# Estl-Board.net
KiCad netlist of a schematic drawn in EAGLE
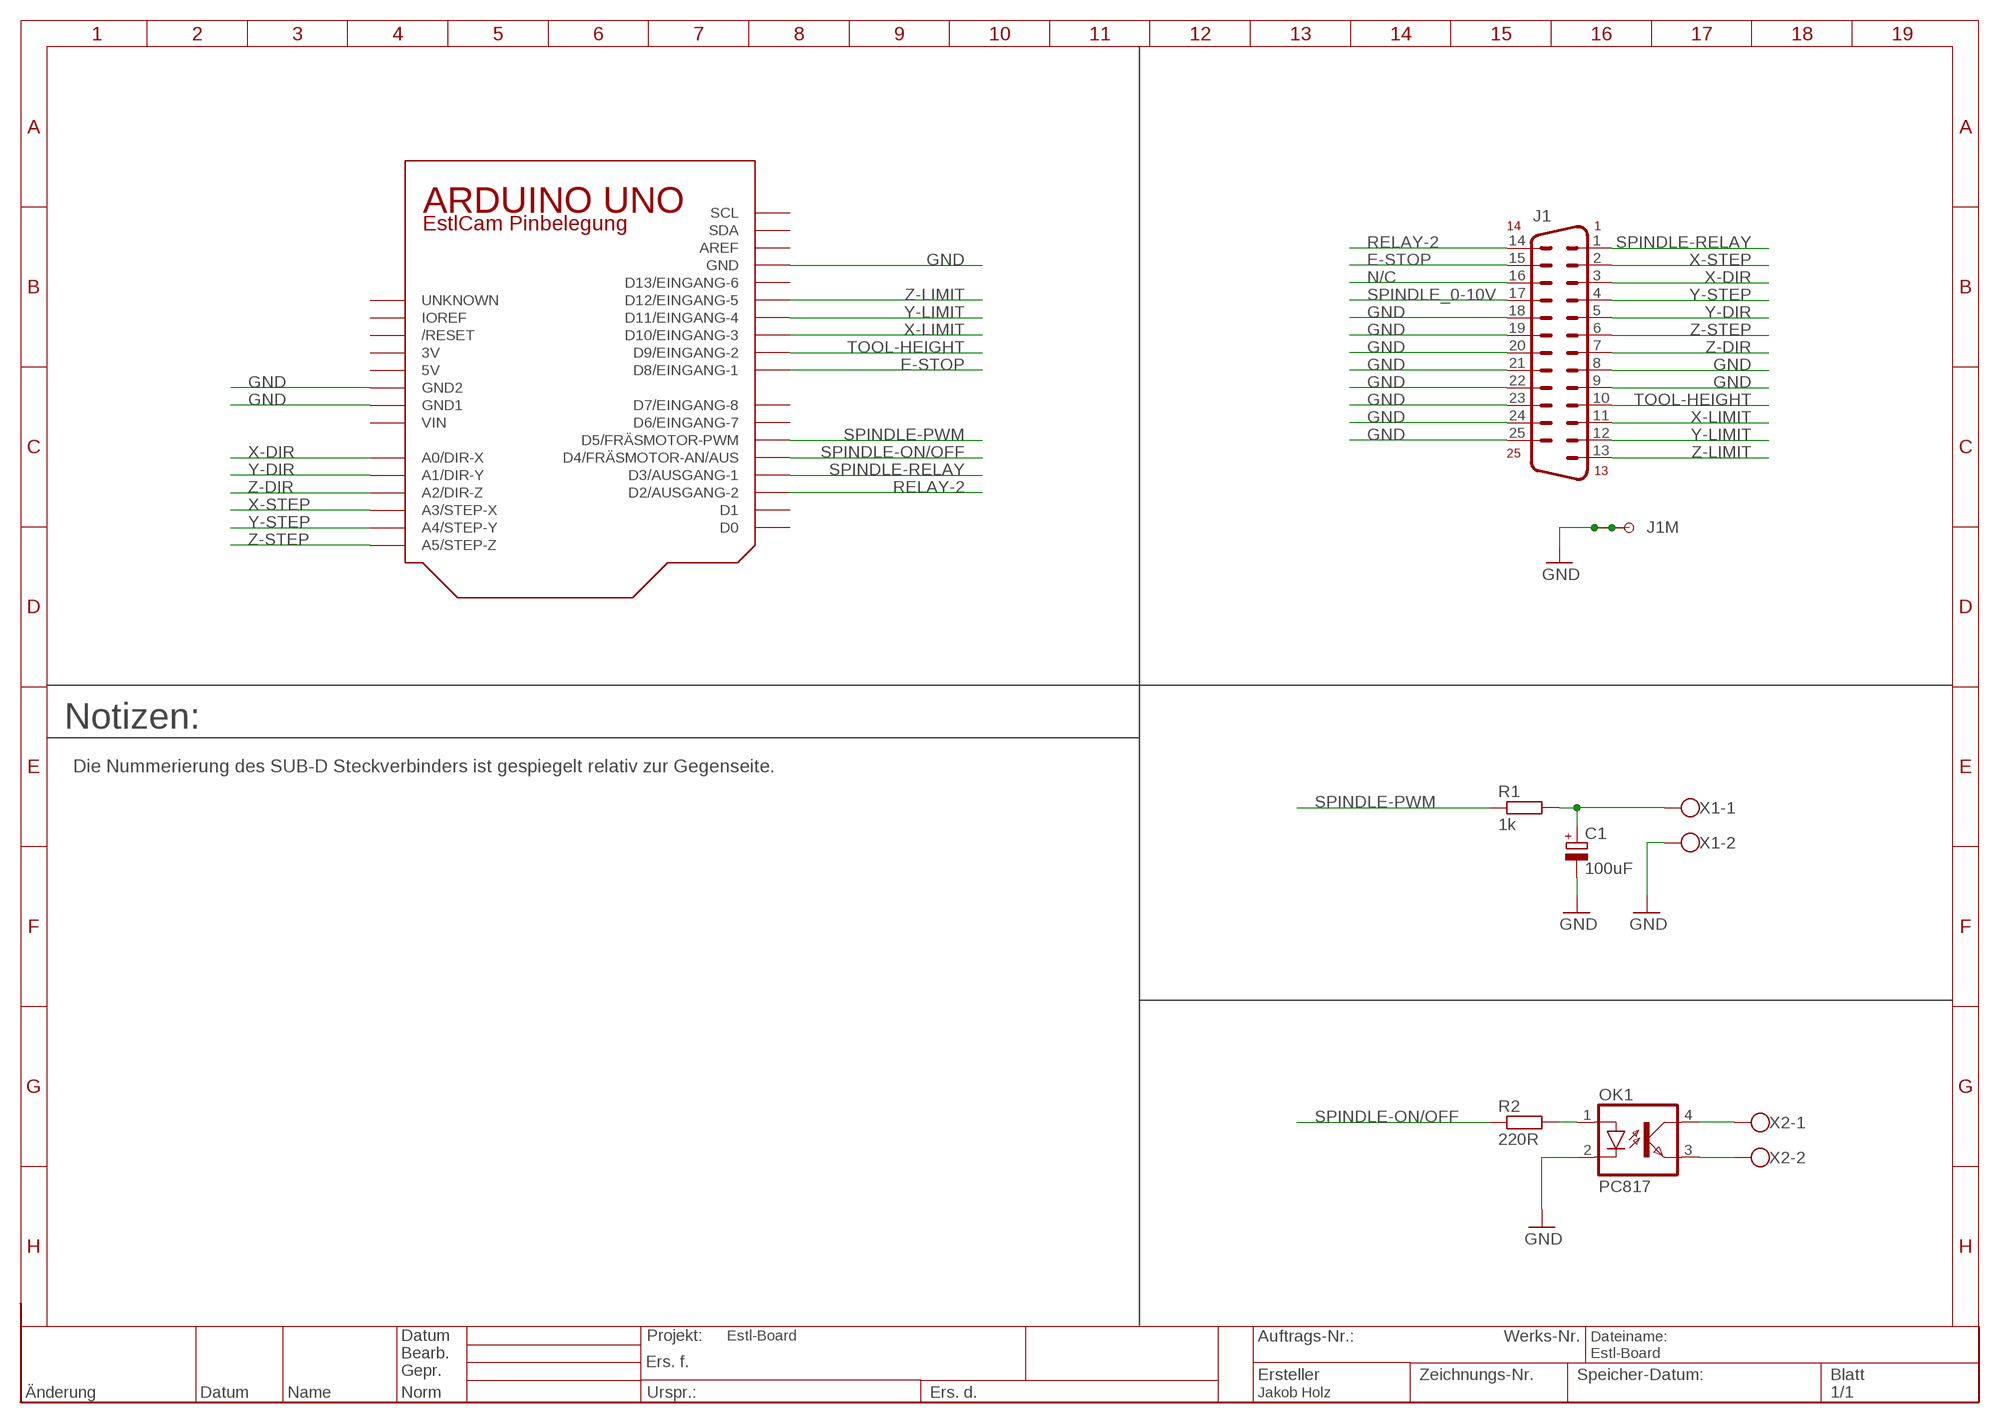
[diagram p0: schematic, sheet 1]

(export (version "E")
  (design (tool "Eeschema 10.0.6"))
  (components
    (comp (ref "C1")
      (value "100uF")
      (footprint "eagle-import:E2-5-CAM")
      (libsource (lib "eagle-import") (part "CPOL-EU-CAM"))
    )
    (comp (ref "IC1")
      (value "ARDUINO")
      (footprint "eagle-import:ARDUINO_NOHOLES")
      (libsource (lib "eagle-import") (part "ARDUINO"))
    )
    (comp (ref "J1")
      (value "JP-316B")
      (footprint "eagle-import:M25HP")
      (libsource (lib "eagle-import") (part "JP-316B"))
    )
    (comp (ref "OK1")
      (value "PC817")
      (footprint "eagle-import:DIP4")
      (libsource (lib "eagle-import") (part "PC817"))
    )
    (comp (ref "R1")
      (value "1k")
      (footprint "eagle-import:207_10+")
      (libsource (lib "eagle-import") (part "R-EU-CAM"))
    )
    (comp (ref "R2")
      (value "220R")
      (footprint "eagle-import:207_10+")
      (libsource (lib "eagle-import") (part "R-EU-CAM"))
    )
    (comp (ref "X1")
      (value "W237-102")
      (footprint "eagle-import:W237-102")
      (fields (field (name "MPN") "237-102"))
      (libsource (lib "eagle-import") (part "W237-102"))
    )
    (comp (ref "X2")
      (value "W237-102")
      (footprint "eagle-import:W237-102")
      (fields (field (name "MPN") "237-102"))
      (libsource (lib "eagle-import") (part "W237-102"))
    )
  )
  (nets
    (net (code "1") (name "/3V") (class "Default")
      (node (ref "IC1") (pin "3V") (pinfunction "3V_3V") (pintype "power_in"))
    )
    (net (code "2") (name "/5V") (class "Default")
      (node (ref "IC1") (pin "5V") (pinfunction "5V_5V") (pintype "power_in"))
    )
    (net (code "3") (name "/E-STOP") (class "Default")
      (node (ref "IC1") (pin "D8") (pinfunction "D8/EINGANG-1_D8") (pintype "bidirectional"))
      (node (ref "J1") (pin "15") (pinfunction "E-STOP_15") (pintype "passive"))
    )
    (net (code "4") (name "/N{slash}C") (class "Default")
      (node (ref "J1") (pin "16") (pinfunction "N/C_16") (pintype "passive"))
    )
    (net (code "5") (name "/RELAY-2") (class "Default")
      (node (ref "IC1") (pin "D2") (pinfunction "D2/AUSGANG-2_D2") (pintype "bidirectional"))
      (node (ref "J1") (pin "14") (pinfunction "RELAY-2_14") (pintype "passive"))
    )
    (net (code "6") (name "/SPINDLE-ON{slash}OFF") (class "Default")
      (node (ref "IC1") (pin "D4") (pinfunction "D4/FRÄSMOTOR-AN/AUS_D4") (pintype "bidirectional"))
      (node (ref "R2") (pin "1") (pinfunction "1_1") (pintype "passive"))
    )
    (net (code "7") (name "/SPINDLE-PWM") (class "Default")
      (node (ref "IC1") (pin "D5") (pinfunction "D5/FRÄSMOTOR-PWM_D5") (pintype "bidirectional"))
      (node (ref "R1") (pin "1") (pinfunction "1_1") (pintype "passive"))
    )
    (net (code "8") (name "/SPINDLE-RELAY") (class "Default")
      (node (ref "IC1") (pin "D3") (pinfunction "D3/AUSGANG-1_D3") (pintype "bidirectional"))
      (node (ref "J1") (pin "1") (pinfunction "SPINDLE-RELAY_1") (pintype "passive"))
    )
    (net (code "9") (name "/SPINDLE_0-10V") (class "Default")
      (node (ref "J1") (pin "17") (pinfunction "SPINDLE_0-10V_17") (pintype "passive"))
    )
    (net (code "10") (name "/TOOL-HEIGHT") (class "Default")
      (node (ref "IC1") (pin "D9") (pinfunction "D9/EINGANG-2_D9") (pintype "bidirectional"))
      (node (ref "J1") (pin "10") (pinfunction "TOOL-HEIGHT_10") (pintype "passive"))
    )
    (net (code "11") (name "/VIN") (class "Default")
      (node (ref "IC1") (pin "VIN") (pinfunction "VIN_VIN") (pintype "power_in"))
    )
    (net (code "12") (name "/X-DIR") (class "Default")
      (node (ref "IC1") (pin "A0") (pinfunction "A0/DIR-X_A0") (pintype "bidirectional"))
      (node (ref "J1") (pin "3") (pinfunction "X-DIR_3") (pintype "passive"))
    )
    (net (code "13") (name "/X-LIMIT") (class "Default")
      (node (ref "IC1") (pin "D10") (pinfunction "D10/EINGANG-3_D10") (pintype "bidirectional"))
      (node (ref "J1") (pin "11") (pinfunction "X-LIMIT_11") (pintype "passive"))
    )
    (net (code "14") (name "/X-STEP") (class "Default")
      (node (ref "IC1") (pin "A3") (pinfunction "A3/STEP-X_A3") (pintype "bidirectional"))
      (node (ref "J1") (pin "2") (pinfunction "X-STEP_2") (pintype "passive"))
    )
    (net (code "15") (name "/Y-DIR") (class "Default")
      (node (ref "IC1") (pin "A1") (pinfunction "A1/DIR-Y_A1") (pintype "bidirectional"))
      (node (ref "J1") (pin "5") (pinfunction "Y-DIR_5") (pintype "passive"))
    )
    (net (code "16") (name "/Y-LIMIT") (class "Default")
      (node (ref "IC1") (pin "D11") (pinfunction "D11/EINGANG-4_D11") (pintype "bidirectional"))
      (node (ref "J1") (pin "12") (pinfunction "Y-LIMIT_12") (pintype "passive"))
    )
    (net (code "17") (name "/Y-STEP") (class "Default")
      (node (ref "IC1") (pin "A4") (pinfunction "A4/STEP-Y_A4") (pintype "bidirectional"))
      (node (ref "J1") (pin "4") (pinfunction "Y-STEP_4") (pintype "passive"))
    )
    (net (code "18") (name "/Z-DIR") (class "Default")
      (node (ref "IC1") (pin "A2") (pinfunction "A2/DIR-Z_A2") (pintype "bidirectional"))
      (node (ref "J1") (pin "7") (pinfunction "Z-DIR_7") (pintype "passive"))
    )
    (net (code "19") (name "/Z-LIMIT") (class "Default")
      (node (ref "IC1") (pin "D12") (pinfunction "D12/EINGANG-5_D12") (pintype "bidirectional"))
      (node (ref "J1") (pin "13") (pinfunction "Z-LIMIT_13") (pintype "passive"))
    )
    (net (code "20") (name "/Z-STEP") (class "Default")
      (node (ref "IC1") (pin "A5") (pinfunction "A5/STEP-Z_A5") (pintype "bidirectional"))
      (node (ref "J1") (pin "6") (pinfunction "Z-STEP_6") (pintype "passive"))
    )
    (net (code "21") (name "GND") (class "Default")
      (node (ref "C1") (pin "-") (pinfunction "-_-") (pintype "passive"))
      (node (ref "IC1") (pin "GND") (pinfunction "GND_GND") (pintype "power_in"))
      (node (ref "IC1") (pin "GND1") (pinfunction "GND1_GND1") (pintype "power_in"))
      (node (ref "IC1") (pin "GND2") (pinfunction "GND2_GND2") (pintype "power_in"))
      (node (ref "J1") (pin "18") (pinfunction "GND0_18") (pintype "passive"))
      (node (ref "J1") (pin "19") (pinfunction "GND1_19") (pintype "passive"))
      (node (ref "J1") (pin "20") (pinfunction "GND2_20") (pintype "passive"))
      (node (ref "J1") (pin "21") (pinfunction "GND3_21") (pintype "passive"))
      (node (ref "J1") (pin "22") (pinfunction "GND4_22") (pintype "passive"))
      (node (ref "J1") (pin "23") (pinfunction "GND5_23") (pintype "passive"))
      (node (ref "J1") (pin "24") (pinfunction "GND6_24") (pintype "passive"))
      (node (ref "J1") (pin "25") (pinfunction "GND7_25") (pintype "passive"))
      (node (ref "J1") (pin "8") (pinfunction "A-STEP_8") (pintype "passive"))
      (node (ref "J1") (pin "9") (pinfunction "A-DIR_9") (pintype "passive"))
      (node (ref "J1") (pin "G1") (pinfunction "G1_G1") (pintype "passive"))
      (node (ref "J1") (pin "G2") (pinfunction "G2_G2") (pintype "passive"))
      (node (ref "OK1") (pin "2") (pinfunction "C_2") (pintype "passive"))
      (node (ref "X1") (pin "2") (pinfunction "KL_2") (pintype "passive"))
    )
    (net (code "22") (name "Net-(OK1-A)") (class "Default")
      (node (ref "OK1") (pin "1") (pinfunction "A_1") (pintype "passive"))
      (node (ref "R2") (pin "2") (pinfunction "2_2") (pintype "passive"))
    )
    (net (code "23") (name "Net-(OK1-COL)") (class "Default")
      (node (ref "OK1") (pin "4") (pinfunction "COL_4") (pintype "passive"))
      (node (ref "X2") (pin "1") (pinfunction "KL_1") (pintype "passive"))
    )
    (net (code "24") (name "Net-(OK1-EMIT)") (class "Default")
      (node (ref "OK1") (pin "3") (pinfunction "EMIT_3") (pintype "passive"))
      (node (ref "X2") (pin "2") (pinfunction "KL_2") (pintype "passive"))
    )
    (net (code "25") (name "Net-(X1A-KL)") (class "Default")
      (node (ref "C1") (pin "+") (pinfunction "+_+") (pintype "passive"))
      (node (ref "R1") (pin "2") (pinfunction "2_2") (pintype "passive"))
      (node (ref "X1") (pin "1") (pinfunction "KL_1") (pintype "passive"))
    )
    (net (code "26") (name "unconnected-(IC1-D6{slash}EINGANG-7-PadD6)") (class "Default")
      (node (ref "IC1") (pin "D6") (pinfunction "D6/EINGANG-7_D6") (pintype "bidirectional"))
    )
    (net (code "27") (name "unconnected-(IC1-D7{slash}EINGANG-8-PadD7)") (class "Default")
      (node (ref "IC1") (pin "D7") (pinfunction "D7/EINGANG-8_D7") (pintype "bidirectional"))
    )
    (net (code "28") (name "unconnected-(IC1-D13{slash}EINGANG-6-PadD13)") (class "Default")
      (node (ref "IC1") (pin "D13") (pinfunction "D13/EINGANG-6_D13") (pintype "bidirectional"))
    )
    (net (code "29") (name "unconnected-(IC1-PadAREF)") (class "Default")
      (node (ref "IC1") (pin "AREF") (pinfunction "AREF_AREF") (pintype "bidirectional"))
    )
    (net (code "30") (name "unconnected-(IC1-PadD0)") (class "Default")
      (node (ref "IC1") (pin "D0") (pinfunction "D0_D0") (pintype "bidirectional"))
    )
    (net (code "31") (name "unconnected-(IC1-PadD1)") (class "Default")
      (node (ref "IC1") (pin "D1") (pinfunction "D1_D1") (pintype "bidirectional"))
    )
    (net (code "32") (name "unconnected-(IC1-PadIOREF)") (class "Default")
      (node (ref "IC1") (pin "IOREF") (pinfunction "IOREF_IOREF") (pintype "bidirectional"))
    )
    (net (code "33") (name "unconnected-(IC1-PadSCL)") (class "Default")
      (node (ref "IC1") (pin "SCL") (pinfunction "SCL_SCL") (pintype "bidirectional"))
    )
    (net (code "34") (name "unconnected-(IC1-PadSDA)") (class "Default")
      (node (ref "IC1") (pin "SDA") (pinfunction "SDA_SDA") (pintype "bidirectional"))
    )
    (net (code "35") (name "unconnected-(IC1-UNKNOWN-Pad!KNOW1)") (class "Default")
      (node (ref "IC1") (pin "!KNOW1") (pinfunction "UNKNOWN_!KNOW1") (pintype "bidirectional"))
    )
    (net (code "36") (name "unconnected-(IC1-{slash}RESET-PadRESET)") (class "Default")
      (node (ref "IC1") (pin "RESET") (pinfunction "/RESET_RESET") (pintype "bidirectional"))
    )
  )
)
